# M3_Coral.net
KiCad netlist of a schematic drawn in Altium Designer
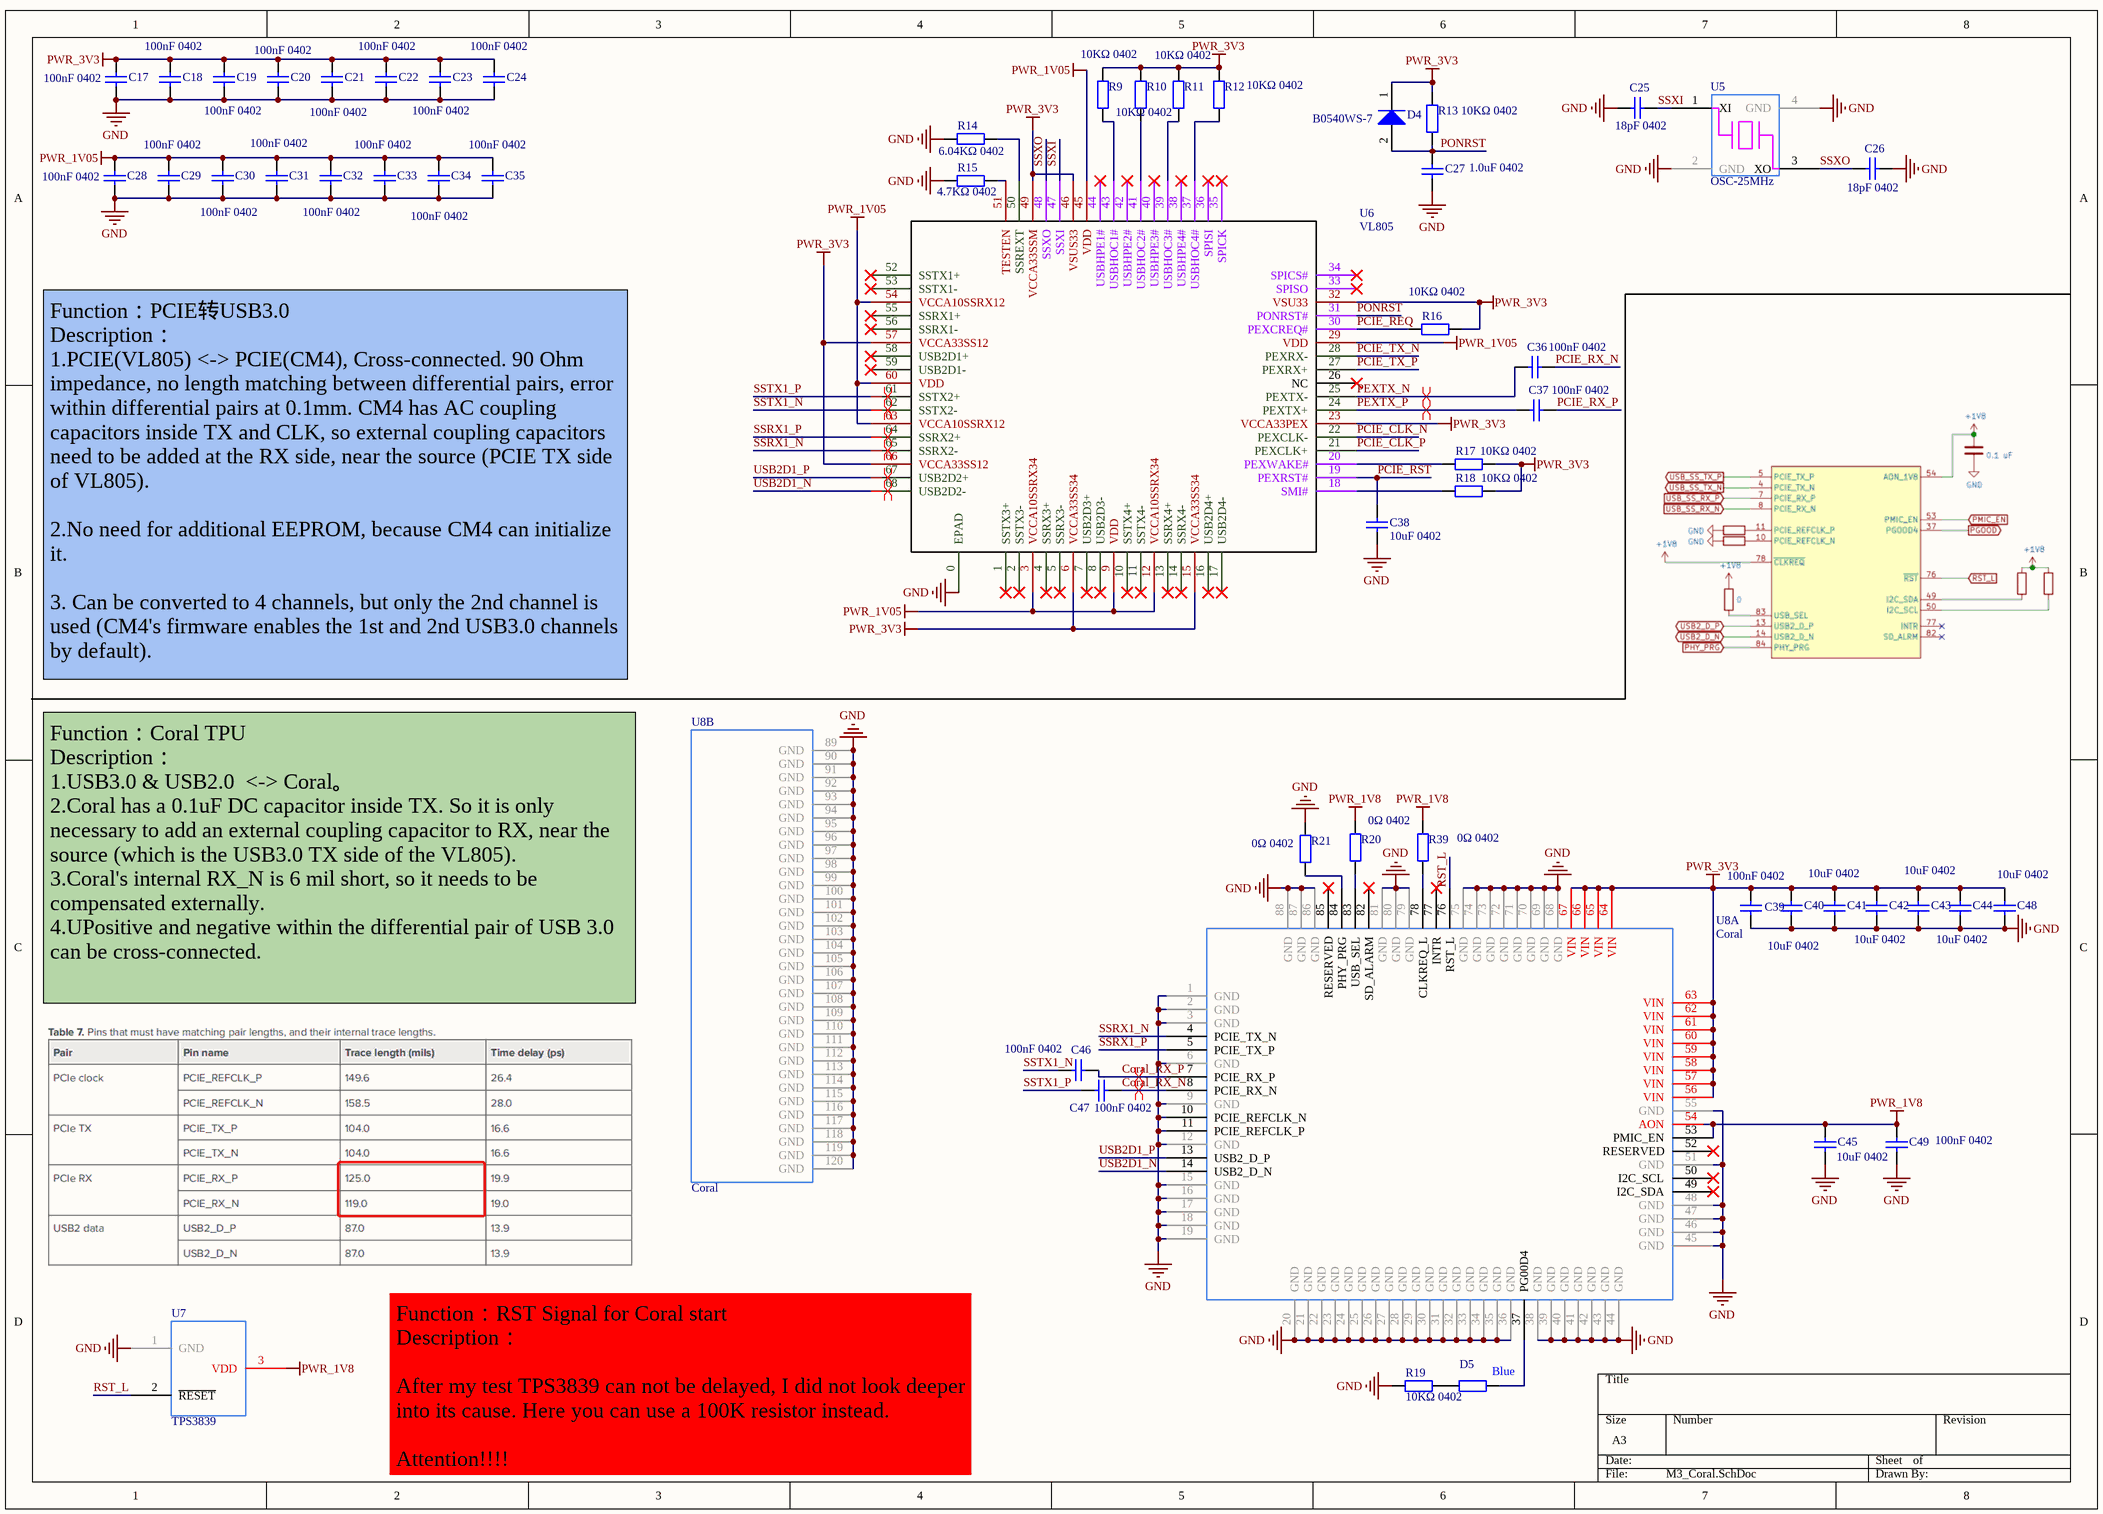
[diagram p0: M3_Coral.SchDoc]

(export (version "E")
  (design (tool "Eeschema 10.0.6"))
  (components
    (comp (ref "C17")
      (value "100nF 0402")
      (footprint "0402_C")
      (description "贴片电容")
      (libsource (lib "Miscellaneous Devices LC") (part "0402 100nF (104) 10% 16V"))
    )
    (comp (ref "C18")
      (value "100nF 0402")
      (footprint "0402_C")
      (description "贴片电容")
      (libsource (lib "Miscellaneous Devices LC") (part "0402 100nF (104) 10% 16V"))
    )
    (comp (ref "C19")
      (value "100nF 0402")
      (footprint "0402_C")
      (description "贴片电容")
      (libsource (lib "Miscellaneous Devices LC") (part "0402 100nF (104) 10% 16V"))
    )
    (comp (ref "C20")
      (value "100nF 0402")
      (footprint "0402_C")
      (description "贴片电容")
      (libsource (lib "Miscellaneous Devices LC") (part "0402 100nF (104) 10% 16V"))
    )
    (comp (ref "C21")
      (value "100nF 0402")
      (footprint "0402_C")
      (description "贴片电容")
      (libsource (lib "Miscellaneous Devices LC") (part "0402 100nF (104) 10% 16V"))
    )
    (comp (ref "C22")
      (value "100nF 0402")
      (footprint "0402_C")
      (description "贴片电容")
      (libsource (lib "Miscellaneous Devices LC") (part "0402 100nF (104) 10% 16V"))
    )
    (comp (ref "C23")
      (value "100nF 0402")
      (footprint "0402_C")
      (description "贴片电容")
      (libsource (lib "Miscellaneous Devices LC") (part "0402 100nF (104) 10% 16V"))
    )
    (comp (ref "C24")
      (value "100nF 0402")
      (footprint "0402_C")
      (description "贴片电容")
      (libsource (lib "Miscellaneous Devices LC") (part "0402 100nF (104) 10% 16V"))
    )
    (comp (ref "C25")
      (value "18pF 0402")
      (footprint "0402_C")
      (description "贴片电容")
      (libsource (lib "Miscellaneous Devices LC") (part "0402 18pF (180) 5% 50V"))
    )
    (comp (ref "C26")
      (value "18pF 0402")
      (footprint "0402_C")
      (description "贴片电容")
      (libsource (lib "Miscellaneous Devices LC") (part "0402 18pF (180) 5% 50V"))
    )
    (comp (ref "C27")
      (value "1.0uF 0402")
      (footprint "0402_C")
      (description "贴片电容")
      (libsource (lib "Miscellaneous Devices LC") (part "0402 1.0uF (105) 10% 25V"))
    )
    (comp (ref "C28")
      (value "100nF 0402")
      (footprint "0402_C")
      (description "贴片电容")
      (libsource (lib "Miscellaneous Devices LC") (part "0402 100nF (104) 10% 16V"))
    )
    (comp (ref "C29")
      (value "100nF 0402")
      (footprint "0402_C")
      (description "贴片电容")
      (libsource (lib "Miscellaneous Devices LC") (part "0402 100nF (104) 10% 16V"))
    )
    (comp (ref "C30")
      (value "100nF 0402")
      (footprint "0402_C")
      (description "贴片电容")
      (libsource (lib "Miscellaneous Devices LC") (part "0402 100nF (104) 10% 16V"))
    )
    (comp (ref "C31")
      (value "100nF 0402")
      (footprint "0402_C")
      (description "贴片电容")
      (libsource (lib "Miscellaneous Devices LC") (part "0402 100nF (104) 10% 16V"))
    )
    (comp (ref "C32")
      (value "100nF 0402")
      (footprint "0402_C")
      (description "贴片电容")
      (libsource (lib "Miscellaneous Devices LC") (part "0402 100nF (104) 10% 16V"))
    )
    (comp (ref "C33")
      (value "100nF 0402")
      (footprint "0402_C")
      (description "贴片电容")
      (libsource (lib "Miscellaneous Devices LC") (part "0402 100nF (104) 10% 16V"))
    )
    (comp (ref "C34")
      (value "100nF 0402")
      (footprint "0402_C")
      (description "贴片电容")
      (libsource (lib "Miscellaneous Devices LC") (part "0402 100nF (104) 10% 16V"))
    )
    (comp (ref "C35")
      (value "100nF 0402")
      (footprint "0402_C")
      (description "贴片电容")
      (libsource (lib "Miscellaneous Devices LC") (part "0402 100nF (104) 10% 16V"))
    )
    (comp (ref "C36")
      (value "100nF 0402")
      (footprint "0402_C")
      (description "贴片电容")
      (libsource (lib "Miscellaneous Devices LC") (part "0402 100nF (104) 10% 16V"))
    )
    (comp (ref "C37")
      (value "100nF 0402")
      (footprint "0402_C")
      (description "贴片电容")
      (libsource (lib "Miscellaneous Devices LC") (part "0402 100nF (104) 10% 16V"))
    )
    (comp (ref "C38")
      (value "10uF 0402")
      (footprint "0402_C")
      (description "贴片电容")
      (libsource (lib "Miscellaneous Devices LC") (part "0402 10uF (106) 20% 6.3V"))
    )
    (comp (ref "C39")
      (value "100nF 0402")
      (footprint "0402_C")
      (description "贴片电容")
      (libsource (lib "Miscellaneous Devices LC") (part "0402 100nF (104) 10% 16V"))
    )
    (comp (ref "C40")
      (value "10uF 0402")
      (footprint "0402_C")
      (description "贴片电容")
      (libsource (lib "Miscellaneous Devices LC") (part "0402 10uF (106) 20% 6.3V"))
    )
    (comp (ref "C41")
      (value "10uF 0402")
      (footprint "0402_C")
      (description "贴片电容")
      (libsource (lib "Miscellaneous Devices LC") (part "0402 10uF (106) 20% 6.3V"))
    )
    (comp (ref "C42")
      (value "10uF 0402")
      (footprint "0402_C")
      (description "贴片电容")
      (libsource (lib "Miscellaneous Devices LC") (part "0402 10uF (106) 20% 6.3V"))
    )
    (comp (ref "C43")
      (value "10uF 0402")
      (footprint "0402_C")
      (description "贴片电容")
      (libsource (lib "Miscellaneous Devices LC") (part "0402 10uF (106) 20% 6.3V"))
    )
    (comp (ref "C44")
      (value "10uF 0402")
      (footprint "0402_C")
      (description "贴片电容")
      (libsource (lib "Miscellaneous Devices LC") (part "0402 10uF (106) 20% 6.3V"))
    )
    (comp (ref "C45")
      (value "10uF 0402")
      (footprint "0402_C")
      (description "贴片电容")
      (libsource (lib "Miscellaneous Devices LC") (part "0402 10uF (106) 20% 6.3V"))
    )
    (comp (ref "C46")
      (value "100nF 0402")
      (footprint "0402_C")
      (description "贴片电容")
      (libsource (lib "Miscellaneous Devices LC") (part "0402 100nF (104) 10% 16V"))
    )
    (comp (ref "C47")
      (value "100nF 0402")
      (footprint "0402_C")
      (description "贴片电容")
      (libsource (lib "Miscellaneous Devices LC") (part "0402 100nF (104) 10% 16V"))
    )
    (comp (ref "C48")
      (value "10uF 0402")
      (footprint "0402_C")
      (description "贴片电容")
      (libsource (lib "Miscellaneous Devices LC") (part "0402 10uF (106) 20% 6.3V"))
    )
    (comp (ref "C49")
      (value "100nF 0402")
      (footprint "0402_C")
      (description "贴片电容")
      (libsource (lib "Miscellaneous Devices LC") (part "0402 100nF (104) 10% 16V"))
    )
    (comp (ref "D4") (value "B0540WS-7") (footprint "B0540WS-7") (libsource (lib "Mars") (part "B0540WS-7")))
    (comp (ref "D5")
      (value "Blue")
      (footprint "0402_R")
      (description "贴片电阻")
      (libsource (lib "") (part "0402 10KΩ (1002) 1%_1"))
    )
    (comp (ref "R9")
      (value "10KΩ 0402")
      (footprint "0402_R")
      (description "贴片电阻")
      (libsource (lib "Miscellaneous Devices LC") (part "0402 10KΩ (1002) 1%"))
    )
    (comp (ref "R10")
      (value "10KΩ 0402")
      (footprint "0402_R")
      (description "贴片电阻")
      (libsource (lib "Miscellaneous Devices LC") (part "0402 10KΩ (1002) 1%"))
    )
    (comp (ref "R11")
      (value "10KΩ 0402")
      (footprint "0402_R")
      (description "贴片电阻")
      (libsource (lib "Miscellaneous Devices LC") (part "0402 10KΩ (1002) 1%"))
    )
    (comp (ref "R12")
      (value "10KΩ 0402")
      (footprint "0402_R")
      (description "贴片电阻")
      (libsource (lib "Miscellaneous Devices LC") (part "0402 10KΩ (1002) 1%"))
    )
    (comp (ref "R13")
      (value "10KΩ 0402")
      (footprint "0402_R")
      (description "贴片电阻")
      (libsource (lib "Miscellaneous Devices LC") (part "0402 10KΩ (1002) 1%"))
    )
    (comp (ref "R14")
      (value "6.04KΩ 0402")
      (footprint "0402_R")
      (description "贴片电阻")
      (libsource (lib "Miscellaneous Devices LC") (part "0402 5.6KΩ (5601) 1%"))
    )
    (comp (ref "R15")
      (value "4.7KΩ 0402")
      (footprint "0402_R")
      (description "贴片电阻")
      (libsource (lib "Miscellaneous Devices LC") (part "0402 4.7KΩ (4701) 1%"))
    )
    (comp (ref "R16")
      (value "10KΩ 0402")
      (footprint "0402_R")
      (description "贴片电阻")
      (libsource (lib "") (part "0402 10KΩ (1002) 1%_1"))
    )
    (comp (ref "R17")
      (value "10KΩ 0402")
      (footprint "0402_R")
      (description "贴片电阻")
      (libsource (lib "") (part "0402 10KΩ (1002) 1%_1"))
    )
    (comp (ref "R18")
      (value "10KΩ 0402")
      (footprint "0402_R")
      (description "贴片电阻")
      (libsource (lib "") (part "0402 10KΩ (1002) 1%_1"))
    )
    (comp (ref "R19")
      (value "10KΩ 0402")
      (footprint "0402_R")
      (description "贴片电阻")
      (libsource (lib "") (part "0402 10KΩ (1002) 1%_1"))
    )
    (comp (ref "R20")
      (value "0Ω 0402")
      (footprint "0402_R")
      (description "贴片电阻")
      (libsource (lib "Miscellaneous Devices LC") (part "0402 0Ω (0R0) 1%"))
    )
    (comp (ref "R21")
      (value "0Ω 0402")
      (footprint "0402_R")
      (description "贴片电阻")
      (libsource (lib "Miscellaneous Devices LC") (part "0402 0Ω (0R0) 1%"))
    )
    (comp (ref "R39")
      (value "0Ω 0402")
      (footprint "0402_R")
      (description "贴片电阻")
      (libsource (lib "Miscellaneous Devices LC") (part "0402 0Ω (0R0) 1%"))
    )
    (comp (ref "U5")
      (value "OSC-25MHz")
      (footprint "OSC-25MHz")
      (description "Passive crystal oscillator")
      (libsource (lib "Mars") (part "OSC-25MHz"))
    )
    (comp (ref "U6")
      (value "VL805")
      (footprint "VL805")
      (description "PCIe to USB3.0")
      (libsource (lib "Mars") (part "VL805"))
    )
    (comp (ref "U7")
      (value "TPS3839")
      (footprint "TPS3839")
      (description "Delay 200 MS")
      (libsource (lib "Mars") (part "TPS3839"))
    )
    (comp (ref "U8")
      (value "Coral")
      (footprint "Coral")
      (description "G313-06329-00")
      (libsource (lib "Mars") (part "Coral"))
    )
  )
  (nets
    (net (code "1") (name "/Coral_RX_N") (class "Default")
      (node (ref "C47") (pin "2") (pinfunction "2_2") (pintype "passive"))
      (node (ref "U8") (pin "8") (pinfunction "PCIE_RX_N_8") (pintype "passive"))
    )
    (net (code "2") (name "/Coral_RX_P") (class "Default")
      (node (ref "C46") (pin "2") (pinfunction "2_2") (pintype "passive"))
      (node (ref "U8") (pin "7") (pinfunction "PCIE_RX_P_7") (pintype "passive"))
    )
    (net (code "3") (name "/PCIE_CLK_N") (class "Default")
      (node (ref "U6") (pin "22") (pinfunction "PEXCLK-_22") (pintype "passive"))
    )
    (net (code "4") (name "/PCIE_CLK_P") (class "Default")
      (node (ref "U6") (pin "21") (pinfunction "PEXCLK+_21") (pintype "passive"))
    )
    (net (code "5") (name "/PCIE_REQ") (class "Default")
      (node (ref "R16") (pin "1") (pinfunction "1_1") (pintype "passive"))
      (node (ref "U6") (pin "30") (pinfunction "PEXCREQ#_30") (pintype "passive"))
    )
    (net (code "6") (name "/PCIE_RST") (class "Default")
      (node (ref "C38") (pin "2") (pinfunction "2_2") (pintype "passive"))
      (node (ref "U6") (pin "19") (pinfunction "PEXRST#_19") (pintype "passive"))
    )
    (net (code "7") (name "/PCIE_RX_N") (class "Default")
      (node (ref "C36") (pin "2") (pinfunction "2_2") (pintype "passive"))
    )
    (net (code "8") (name "/PCIE_RX_P") (class "Default")
      (node (ref "C37") (pin "2") (pinfunction "2_2") (pintype "passive"))
    )
    (net (code "9") (name "/PCIE_TX_N") (class "Default")
      (node (ref "U6") (pin "28") (pinfunction "PEXRX-_28") (pintype "passive"))
    )
    (net (code "10") (name "/PCIE_TX_P") (class "Default")
      (node (ref "U6") (pin "27") (pinfunction "PEXRX+_27") (pintype "passive"))
    )
    (net (code "11") (name "/PEXTX_N") (class "Default")
      (node (ref "C36") (pin "1") (pinfunction "1_1") (pintype "passive"))
      (node (ref "U6") (pin "25") (pinfunction "PEXTX-_25") (pintype "passive"))
    )
    (net (code "12") (name "/PEXTX_P") (class "Default")
      (node (ref "C37") (pin "1") (pinfunction "1_1") (pintype "passive"))
      (node (ref "U6") (pin "24") (pinfunction "PEXTX+_24") (pintype "passive"))
    )
    (net (code "13") (name "/PONRST") (class "Default")
      (node (ref "C27") (pin "1") (pinfunction "1_1") (pintype "passive"))
      (node (ref "D4") (pin "2") (pinfunction "A_2") (pintype "passive"))
      (node (ref "R13") (pin "1") (pinfunction "1_1") (pintype "passive"))
      (node (ref "U6") (pin "31") (pinfunction "PONRST#_31") (pintype "passive"))
    )
    (net (code "14") (name "/RST_L") (class "Default")
      (node (ref "U7") (pin "2") (pinfunction "~{RESET}_2") (pintype "passive"))
      (node (ref "U8") (pin "76") (pinfunction "RST_L_76") (pintype "power_in"))
    )
    (net (code "15") (name "/SSRX1_N") (class "Default")
      (node (ref "U6") (pin "65") (pinfunction "SSRX2-_65") (pintype "passive"))
      (node (ref "U8") (pin "4") (pinfunction "PCIE_TX_N_4") (pintype "passive"))
    )
    (net (code "16") (name "/SSRX1_P") (class "Default")
      (node (ref "U6") (pin "64") (pinfunction "SSRX2+_64") (pintype "passive"))
      (node (ref "U8") (pin "5") (pinfunction "PCIE_TX_P_5") (pintype "passive"))
    )
    (net (code "17") (name "/SSTX1_N") (class "Default")
      (node (ref "C46") (pin "1") (pinfunction "1_1") (pintype "passive"))
      (node (ref "U6") (pin "62") (pinfunction "SSTX2-_62") (pintype "passive"))
    )
    (net (code "18") (name "/SSTX1_P") (class "Default")
      (node (ref "C47") (pin "1") (pinfunction "1_1") (pintype "passive"))
      (node (ref "U6") (pin "61") (pinfunction "SSTX2+_61") (pintype "passive"))
    )
    (net (code "19") (name "/SSXI") (class "Default")
      (node (ref "C25") (pin "2") (pinfunction "2_2") (pintype "passive"))
      (node (ref "U5") (pin "1") (pinfunction "XI_1") (pintype "passive"))
      (node (ref "U6") (pin "47") (pinfunction "SSXI_47") (pintype "passive"))
    )
    (net (code "20") (name "/SSXO") (class "Default")
      (node (ref "C26") (pin "1") (pinfunction "1_1") (pintype "passive"))
      (node (ref "U5") (pin "3") (pinfunction "XO_3") (pintype "passive"))
      (node (ref "U6") (pin "48") (pinfunction "SSXO_48") (pintype "passive"))
    )
    (net (code "21") (name "/USB2D1_N") (class "Default")
      (node (ref "U6") (pin "68") (pinfunction "USB2D2-_68") (pintype "passive"))
      (node (ref "U8") (pin "14") (pinfunction "USB2_D_N_14") (pintype "passive"))
    )
    (net (code "22") (name "/USB2D1_P") (class "Default")
      (node (ref "U6") (pin "67") (pinfunction "USB2D2+_67") (pintype "passive"))
      (node (ref "U8") (pin "13") (pinfunction "USB2_D_P_13") (pintype "passive"))
    )
    (net (code "23") (name "GND") (class "Default")
      (node (ref "C17") (pin "1") (pinfunction "1_1") (pintype "passive"))
      (node (ref "C18") (pin "1") (pinfunction "1_1") (pintype "passive"))
      (node (ref "C19") (pin "1") (pinfunction "1_1") (pintype "passive"))
      (node (ref "C20") (pin "1") (pinfunction "1_1") (pintype "passive"))
      (node (ref "C21") (pin "1") (pinfunction "1_1") (pintype "passive"))
      (node (ref "C22") (pin "1") (pinfunction "1_1") (pintype "passive"))
      (node (ref "C23") (pin "1") (pinfunction "1_1") (pintype "passive"))
      (node (ref "C24") (pin "1") (pinfunction "1_1") (pintype "passive"))
      (node (ref "C25") (pin "1") (pinfunction "1_1") (pintype "passive"))
      (node (ref "C26") (pin "2") (pinfunction "2_2") (pintype "passive"))
      (node (ref "C27") (pin "2") (pinfunction "2_2") (pintype "passive"))
      (node (ref "C28") (pin "1") (pinfunction "1_1") (pintype "passive"))
      (node (ref "C29") (pin "1") (pinfunction "1_1") (pintype "passive"))
      (node (ref "C30") (pin "1") (pinfunction "1_1") (pintype "passive"))
      (node (ref "C31") (pin "1") (pinfunction "1_1") (pintype "passive"))
      (node (ref "C32") (pin "1") (pinfunction "1_1") (pintype "passive"))
      (node (ref "C33") (pin "1") (pinfunction "1_1") (pintype "passive"))
      (node (ref "C34") (pin "1") (pinfunction "1_1") (pintype "passive"))
      (node (ref "C35") (pin "1") (pinfunction "1_1") (pintype "passive"))
      (node (ref "C38") (pin "1") (pinfunction "1_1") (pintype "passive"))
      (node (ref "C39") (pin "1") (pinfunction "1_1") (pintype "passive"))
      (node (ref "C40") (pin "1") (pinfunction "1_1") (pintype "passive"))
      (node (ref "C41") (pin "1") (pinfunction "1_1") (pintype "passive"))
      (node (ref "C42") (pin "1") (pinfunction "1_1") (pintype "passive"))
      (node (ref "C43") (pin "1") (pinfunction "1_1") (pintype "passive"))
      (node (ref "C44") (pin "1") (pinfunction "1_1") (pintype "passive"))
      (node (ref "C45") (pin "1") (pinfunction "1_1") (pintype "passive"))
      (node (ref "C48") (pin "1") (pinfunction "1_1") (pintype "passive"))
      (node (ref "C49") (pin "1") (pinfunction "1_1") (pintype "passive"))
      (node (ref "R14") (pin "2") (pinfunction "2_2") (pintype "passive"))
      (node (ref "R15") (pin "2") (pinfunction "2_2") (pintype "passive"))
      (node (ref "R19") (pin "1") (pinfunction "1_1") (pintype "passive"))
      (node (ref "R21") (pin "2") (pinfunction "2_2") (pintype "passive"))
      (node (ref "U5") (pin "2") (pinfunction "GND_2") (pintype "passive"))
      (node (ref "U5") (pin "4") (pinfunction "GND_4") (pintype "passive"))
      (node (ref "U6") (pin "0") (pinfunction "EPAD_0") (pintype "passive"))
      (node (ref "U7") (pin "1") (pinfunction "GND_1") (pintype "passive"))
      (node (ref "U8") (pin "1") (pinfunction "GND_1") (pintype "power_in"))
      (node (ref "U8") (pin "10") (pinfunction "PCIE_REFCLK_N_10") (pintype "passive"))
      (node (ref "U8") (pin "100") (pinfunction "GND_100") (pintype "power_in"))
      (node (ref "U8") (pin "101") (pinfunction "GND_101") (pintype "power_in"))
      (node (ref "U8") (pin "102") (pinfunction "GND_102") (pintype "power_in"))
      (node (ref "U8") (pin "103") (pinfunction "GND_103") (pintype "power_in"))
      (node (ref "U8") (pin "104") (pinfunction "GND_104") (pintype "power_in"))
      (node (ref "U8") (pin "105") (pinfunction "GND_105") (pintype "power_in"))
      (node (ref "U8") (pin "106") (pinfunction "GND_106") (pintype "power_in"))
      (node (ref "U8") (pin "107") (pinfunction "GND_107") (pintype "power_in"))
      (node (ref "U8") (pin "108") (pinfunction "GND_108") (pintype "power_in"))
      (node (ref "U8") (pin "109") (pinfunction "GND_109") (pintype "power_in"))
      (node (ref "U8") (pin "11") (pinfunction "PCIE_REFCLK_P_11") (pintype "passive"))
      (node (ref "U8") (pin "110") (pinfunction "GND_110") (pintype "power_in"))
      (node (ref "U8") (pin "111") (pinfunction "GND_111") (pintype "power_in"))
      (node (ref "U8") (pin "112") (pinfunction "GND_112") (pintype "power_in"))
      (node (ref "U8") (pin "113") (pinfunction "GND_113") (pintype "power_in"))
      (node (ref "U8") (pin "114") (pinfunction "GND_114") (pintype "power_in"))
      (node (ref "U8") (pin "115") (pinfunction "GND_115") (pintype "power_in"))
      (node (ref "U8") (pin "116") (pinfunction "GND_116") (pintype "power_in"))
      (node (ref "U8") (pin "117") (pinfunction "GND_117") (pintype "power_in"))
      (node (ref "U8") (pin "118") (pinfunction "GND_118") (pintype "power_in"))
      (node (ref "U8") (pin "119") (pinfunction "GND_119") (pintype "power_in"))
      (node (ref "U8") (pin "12") (pinfunction "GND_12") (pintype "passive"))
      (node (ref "U8") (pin "120") (pinfunction "GND_120") (pintype "power_in"))
      (node (ref "U8") (pin "15") (pinfunction "GND_15") (pintype "passive"))
      (node (ref "U8") (pin "16") (pinfunction "GND_16") (pintype "passive"))
      (node (ref "U8") (pin "17") (pinfunction "GND_17") (pintype "passive"))
      (node (ref "U8") (pin "18") (pinfunction "GND_18") (pintype "passive"))
      (node (ref "U8") (pin "19") (pinfunction "GND_19") (pintype "passive"))
      (node (ref "U8") (pin "2") (pinfunction "GND_2") (pintype "passive"))
      (node (ref "U8") (pin "20") (pinfunction "GND_20") (pintype "power_in"))
      (node (ref "U8") (pin "21") (pinfunction "GND_21") (pintype "power_in"))
      (node (ref "U8") (pin "22") (pinfunction "GND_22") (pintype "power_in"))
      (node (ref "U8") (pin "23") (pinfunction "GND_23") (pintype "power_in"))
      (node (ref "U8") (pin "24") (pinfunction "GND_24") (pintype "power_in"))
      (node (ref "U8") (pin "25") (pinfunction "GND_25") (pintype "power_in"))
      (node (ref "U8") (pin "26") (pinfunction "GND_26") (pintype "power_in"))
      (node (ref "U8") (pin "27") (pinfunction "GND_27") (pintype "power_in"))
      (node (ref "U8") (pin "28") (pinfunction "GND_28") (pintype "power_in"))
      (node (ref "U8") (pin "29") (pinfunction "GND_29") (pintype "power_in"))
      (node (ref "U8") (pin "3") (pinfunction "GND_3") (pintype "passive"))
      (node (ref "U8") (pin "30") (pinfunction "GND_30") (pintype "power_in"))
      (node (ref "U8") (pin "31") (pinfunction "GND_31") (pintype "power_in"))
      (node (ref "U8") (pin "32") (pinfunction "GND_32") (pintype "power_in"))
      (node (ref "U8") (pin "33") (pinfunction "GND_33") (pintype "power_in"))
      (node (ref "U8") (pin "34") (pinfunction "GND_34") (pintype "power_in"))
      (node (ref "U8") (pin "35") (pinfunction "GND_35") (pintype "power_in"))
      (node (ref "U8") (pin "36") (pinfunction "GND_36") (pintype "power_in"))
      (node (ref "U8") (pin "38") (pinfunction "GND_38") (pintype "power_in"))
      (node (ref "U8") (pin "39") (pinfunction "GND_39") (pintype "power_in"))
      (node (ref "U8") (pin "40") (pinfunction "GND_40") (pintype "power_in"))
      (node (ref "U8") (pin "41") (pinfunction "GND_41") (pintype "power_in"))
      (node (ref "U8") (pin "42") (pinfunction "GND_42") (pintype "power_in"))
      (node (ref "U8") (pin "43") (pinfunction "GND_43") (pintype "power_in"))
      (node (ref "U8") (pin "44") (pinfunction "GND_44") (pintype "power_in"))
      (node (ref "U8") (pin "45") (pinfunction "GND_45") (pintype "power_in"))
      (node (ref "U8") (pin "46") (pinfunction "GND_46") (pintype "passive"))
      (node (ref "U8") (pin "47") (pinfunction "GND_47") (pintype "passive"))
      (node (ref "U8") (pin "48") (pinfunction "GND_48") (pintype "passive"))
      (node (ref "U8") (pin "51") (pinfunction "GND_51") (pintype "passive"))
      (node (ref "U8") (pin "55") (pinfunction "GND_55") (pintype "passive"))
      (node (ref "U8") (pin "6") (pinfunction "GND_6") (pintype "passive"))
      (node (ref "U8") (pin "68") (pinfunction "GND_68") (pintype "power_in"))
      (node (ref "U8") (pin "69") (pinfunction "GND_69") (pintype "power_in"))
      (node (ref "U8") (pin "70") (pinfunction "GND_70") (pintype "power_in"))
      (node (ref "U8") (pin "71") (pinfunction "GND_71") (pintype "power_in"))
      (node (ref "U8") (pin "72") (pinfunction "GND_72") (pintype "power_in"))
      (node (ref "U8") (pin "73") (pinfunction "GND_73") (pintype "power_in"))
      (node (ref "U8") (pin "74") (pinfunction "GND_74") (pintype "power_in"))
      (node (ref "U8") (pin "75") (pinfunction "GND_75") (pintype "power_in"))
      (node (ref "U8") (pin "79") (pinfunction "GND_79") (pintype "power_in"))
      (node (ref "U8") (pin "80") (pinfunction "GND_80") (pintype "power_in"))
      (node (ref "U8") (pin "81") (pinfunction "GND_81") (pintype "power_in"))
      (node (ref "U8") (pin "86") (pinfunction "GND_86") (pintype "power_in"))
      (node (ref "U8") (pin "87") (pinfunction "GND_87") (pintype "power_in"))
      (node (ref "U8") (pin "88") (pinfunction "GND_88") (pintype "power_in"))
      (node (ref "U8") (pin "89") (pinfunction "GND_89") (pintype "power_in"))
      (node (ref "U8") (pin "9") (pinfunction "GND_9") (pintype "passive"))
      (node (ref "U8") (pin "90") (pinfunction "GND_90") (pintype "power_in"))
      (node (ref "U8") (pin "91") (pinfunction "GND_91") (pintype "power_in"))
      (node (ref "U8") (pin "92") (pinfunction "GND_92") (pintype "power_in"))
      (node (ref "U8") (pin "93") (pinfunction "GND_93") (pintype "power_in"))
      (node (ref "U8") (pin "94") (pinfunction "GND_94") (pintype "power_in"))
      (node (ref "U8") (pin "95") (pinfunction "GND_95") (pintype "power_in"))
      (node (ref "U8") (pin "96") (pinfunction "GND_96") (pintype "power_in"))
      (node (ref "U8") (pin "97") (pinfunction "GND_97") (pintype "power_in"))
      (node (ref "U8") (pin "98") (pinfunction "GND_98") (pintype "power_in"))
      (node (ref "U8") (pin "99") (pinfunction "GND_99") (pintype "power_in"))
    )
    (net (code "24") (name "Net-(D5-Pad1)") (class "Default")
      (node (ref "D5") (pin "1") (pinfunction "1_1") (pintype "passive"))
      (node (ref "R19") (pin "2") (pinfunction "2_2") (pintype "passive"))
    )
    (net (code "25") (name "Net-(U6-PEXWAKE#)") (class "Default")
      (node (ref "R17") (pin "1") (pinfunction "1_1") (pintype "passive"))
      (node (ref "U6") (pin "20") (pinfunction "PEXWAKE#_20") (pintype "passive"))
    )
    (net (code "26") (name "Net-(U6-SMI#)") (class "Default")
      (node (ref "R18") (pin "1") (pinfunction "1_1") (pintype "passive"))
      (node (ref "U6") (pin "18") (pinfunction "SMI#_18") (pintype "passive"))
    )
    (net (code "27") (name "Net-(U6-SSREXT)") (class "Default")
      (node (ref "R14") (pin "1") (pinfunction "1_1") (pintype "passive"))
      (node (ref "U6") (pin "50") (pinfunction "SSREXT_50") (pintype "passive"))
    )
    (net (code "28") (name "Net-(U6-TESTEN)") (class "Default")
      (node (ref "R15") (pin "1") (pinfunction "1_1") (pintype "passive"))
      (node (ref "U6") (pin "51") (pinfunction "TESTEN_51") (pintype "passive"))
    )
    (net (code "29") (name "Net-(U6-USBHOC1#)") (class "Default")
      (node (ref "R9") (pin "1") (pinfunction "1_1") (pintype "passive"))
      (node (ref "U6") (pin "43") (pinfunction "USBHOC1#_43") (pintype "passive"))
    )
    (net (code "30") (name "Net-(U6-USBHOC2#)") (class "Default")
      (node (ref "R10") (pin "1") (pinfunction "1_1") (pintype "passive"))
      (node (ref "U6") (pin "41") (pinfunction "USBHOC2#_41") (pintype "passive"))
    )
    (net (code "31") (name "Net-(U6-USBHOC3#)") (class "Default")
      (node (ref "R11") (pin "1") (pinfunction "1_1") (pintype "passive"))
      (node (ref "U6") (pin "39") (pinfunction "USBHOC3#_39") (pintype "passive"))
    )
    (net (code "32") (name "Net-(U6-USBHOC4#)") (class "Default")
      (node (ref "R12") (pin "1") (pinfunction "1_1") (pintype "passive"))
      (node (ref "U6") (pin "37") (pinfunction "USBHOC4#_37") (pintype "passive"))
    )
    (net (code "33") (name "Net-(U8A-CLKREQ_L)") (class "Default")
      (node (ref "R39") (pin "1") (pinfunction "1_1") (pintype "passive"))
      (node (ref "U8") (pin "78") (pinfunction "CLKREQ_L_78") (pintype "power_in"))
    )
    (net (code "34") (name "Net-(U8A-PG00D4)") (class "Default")
      (node (ref "D5") (pin "2") (pinfunction "2_2") (pintype "passive"))
      (node (ref "U8") (pin "37") (pinfunction "PG00D4_37") (pintype "power_in"))
    )
    (net (code "35") (name "Net-(U8A-PHY_PRG)") (class "Default")
      (node (ref "R21") (pin "1") (pinfunction "1_1") (pintype "passive"))
      (node (ref "U8") (pin "84") (pinfunction "PHY_PRG_84") (pintype "power_in"))
    )
    (net (code "36") (name "Net-(U8A-USB_SEL)") (class "Default")
      (node (ref "R20") (pin "1") (pinfunction "1_1") (pintype "passive"))
      (node (ref "U8") (pin "83") (pinfunction "USB_SEL_83") (pintype "power_in"))
    )
    (net (code "37") (name "PWR_1V05") (class "Default")
      (node (ref "C28") (pin "2") (pinfunction "2_2") (pintype "passive"))
      (node (ref "C29") (pin "2") (pinfunction "2_2") (pintype "passive"))
      (node (ref "C30") (pin "2") (pinfunction "2_2") (pintype "passive"))
      (node (ref "C31") (pin "2") (pinfunction "2_2") (pintype "passive"))
      (node (ref "C32") (pin "2") (pinfunction "2_2") (pintype "passive"))
      (node (ref "C33") (pin "2") (pinfunction "2_2") (pintype "passive"))
      (node (ref "C34") (pin "2") (pinfunction "2_2") (pintype "passive"))
      (node (ref "C35") (pin "2") (pinfunction "2_2") (pintype "passive"))
      (node (ref "U6") (pin "12") (pinfunction "VCCA10SSRX34_12") (pintype "passive"))
      (node (ref "U6") (pin "29") (pinfunction "VDD_29") (pintype "passive"))
      (node (ref "U6") (pin "3") (pinfunction "VCCA10SSRX34_3") (pintype "passive"))
      (node (ref "U6") (pin "45") (pinfunction "VDD_45") (pintype "passive"))
      (node (ref "U6") (pin "54") (pinfunction "VCCA10SSRX12_54") (pintype "passive"))
      (node (ref "U6") (pin "60") (pinfunction "VDD_60") (pintype "passive"))
      (node (ref "U6") (pin "63") (pinfunction "VCCA10SSRX12_63") (pintype "passive"))
      (node (ref "U6") (pin "9") (pinfunction "VDD_9") (pintype "passive"))
    )
    (net (code "38") (name "PWR_1V8") (class "Default")
      (node (ref "C45") (pin "2") (pinfunction "2_2") (pintype "passive"))
      (node (ref "C49") (pin "2") (pinfunction "2_2") (pintype "passive"))
      (node (ref "R20") (pin "2") (pinfunction "2_2") (pintype "passive"))
      (node (ref "R39") (pin "2") (pinfunction "2_2") (pintype "passive"))
      (node (ref "U7") (pin "3") (pinfunction "VDD_3") (pintype "passive"))
      (node (ref "U8") (pin "53") (pinfunction "PMIC_EN_53") (pintype "passive"))
      (node (ref "U8") (pin "54") (pinfunction "AON_54") (pintype "passive"))
    )
    (net (code "39") (name "PWR_3V3") (class "Default")
      (node (ref "C17") (pin "2") (pinfunction "2_2") (pintype "passive"))
      (node (ref "C18") (pin "2") (pinfunction "2_2") (pintype "passive"))
      (node (ref "C19") (pin "2") (pinfunction "2_2") (pintype "passive"))
      (node (ref "C20") (pin "2") (pinfunction "2_2") (pintype "passive"))
      (node (ref "C21") (pin "2") (pinfunction "2_2") (pintype "passive"))
      (node (ref "C22") (pin "2") (pinfunction "2_2") (pintype "passive"))
      (node (ref "C23") (pin "2") (pinfunction "2_2") (pintype "passive"))
      (node (ref "C24") (pin "2") (pinfunction "2_2") (pintype "passive"))
      (node (ref "C39") (pin "2") (pinfunction "2_2") (pintype "passive"))
      (node (ref "C40") (pin "2") (pinfunction "2_2") (pintype "passive"))
      (node (ref "C41") (pin "2") (pinfunction "2_2") (pintype "passive"))
      (node (ref "C42") (pin "2") (pinfunction "2_2") (pintype "passive"))
      (node (ref "C43") (pin "2") (pinfunction "2_2") (pintype "passive"))
      (node (ref "C44") (pin "2") (pinfunction "2_2") (pintype "passive"))
      (node (ref "C48") (pin "2") (pinfunction "2_2") (pintype "passive"))
      (node (ref "D4") (pin "1") (pinfunction "K_1") (pintype "passive"))
      (node (ref "R10") (pin "2") (pinfunction "2_2") (pintype "passive"))
      (node (ref "R11") (pin "2") (pinfunction "2_2") (pintype "passive"))
      (node (ref "R12") (pin "2") (pinfunction "2_2") (pintype "passive"))
      (node (ref "R13") (pin "2") (pinfunction "2_2") (pintype "passive"))
      (node (ref "R16") (pin "2") (pinfunction "2_2") (pintype "passive"))
      (node (ref "R17") (pin "2") (pinfunction "2_2") (pintype "passive"))
      (node (ref "R18") (pin "2") (pinfunction "2_2") (pintype "passive"))
      (node (ref "R9") (pin "2") (pinfunction "2_2") (pintype "passive"))
      (node (ref "U6") (pin "15") (pinfunction "VCCA33SS34_15") (pintype "passive"))
      (node (ref "U6") (pin "23") (pinfunction "VCCA33PEX_23") (pintype "passive"))
      (node (ref "U6") (pin "32") (pinfunction "VSU33_32") (pintype "passive"))
      (node (ref "U6") (pin "46") (pinfunction "VSUS33_46") (pintype "passive"))
      (node (ref "U6") (pin "49") (pinfunction "VCCA33SSM_49") (pintype "passive"))
      (node (ref "U6") (pin "57") (pinfunction "VCCA33SS12_57") (pintype "passive"))
      (node (ref "U6") (pin "6") (pinfunction "VCCA33SS34_6") (pintype "passive"))
      (node (ref "U6") (pin "66") (pinfunction "VCCA33SS12_66") (pintype "passive"))
      (node (ref "U8") (pin "56") (pinfunction "VIN_56") (pintype "passive"))
      (node (ref "U8") (pin "57") (pinfunction "VIN_57") (pintype "passive"))
      (node (ref "U8") (pin "58") (pinfunction "VIN_58") (pintype "passive"))
      (node (ref "U8") (pin "59") (pinfunction "VIN_59") (pintype "passive"))
      (node (ref "U8") (pin "60") (pinfunction "VIN_60") (pintype "passive"))
      (node (ref "U8") (pin "61") (pinfunction "VIN_61") (pintype "passive"))
      (node (ref "U8") (pin "62") (pinfunction "VIN_62") (pintype "passive"))
      (node (ref "U8") (pin "63") (pinfunction "VIN_63") (pintype "passive"))
      (node (ref "U8") (pin "64") (pinfunction "VIN_64") (pintype "power_in"))
      (node (ref "U8") (pin "65") (pinfunction "VIN_65") (pintype "power_in"))
      (node (ref "U8") (pin "66") (pinfunction "VIN_66") (pintype "power_in"))
      (node (ref "U8") (pin "67") (pinfunction "VIN_67") (pintype "power_in"))
    )
    (net (code "40") (name "unconnected-(U6-NC-Pad26)") (class "Default")
      (node (ref "U6") (pin "26") (pinfunction "NC_26") (pintype "passive+no_connect"))
    )
    (net (code "41") (name "unconnected-(U6-SPICK-Pad35)") (class "Default")
      (node (ref "U6") (pin "35") (pinfunction "SPICK_35") (pintype "passive+no_connect"))
    )
    (net (code "42") (name "unconnected-(U6-SPICS#-Pad34)") (class "Default")
      (node (ref "U6") (pin "34") (pinfunction "SPICS#_34") (pintype "passive+no_connect"))
    )
    (net (code "43") (name "unconnected-(U6-SPISI-Pad36)") (class "Default")
      (node (ref "U6") (pin "36") (pinfunction "SPISI_36") (pintype "passive+no_connect"))
    )
    (net (code "44") (name "unconnected-(U6-SPISO-Pad33)") (class "Default")
      (node (ref "U6") (pin "33") (pinfunction "SPISO_33") (pintype "passive+no_connect"))
    )
    (net (code "45") (name "unconnected-(U6-SSRX1+-Pad55)") (class "Default")
      (node (ref "U6") (pin "55") (pinfunction "SSRX1+_55") (pintype "passive+no_connect"))
    )
    (net (code "46") (name "unconnected-(U6-SSRX1--Pad56)") (class "Default")
      (node (ref "U6") (pin "56") (pinfunction "SSRX1-_56") (pintype "passive+no_connect"))
    )
    (net (code "47") (name "unconnected-(U6-SSRX3+-Pad4)") (class "Default")
      (node (ref "U6") (pin "4") (pinfunction "SSRX3+_4") (pintype "passive+no_connect"))
    )
    (net (code "48") (name "unconnected-(U6-SSRX3--Pad5)") (class "Default")
      (node (ref "U6") (pin "5") (pinfunction "SSRX3-_5") (pintype "passive+no_connect"))
    )
    (net (code "49") (name "unconnected-(U6-SSRX4+-Pad13)") (class "Default")
      (node (ref "U6") (pin "13") (pinfunction "SSRX4+_13") (pintype "passive+no_connect"))
    )
    (net (code "50") (name "unconnected-(U6-SSRX4--Pad14)") (class "Default")
      (node (ref "U6") (pin "14") (pinfunction "SSRX4-_14") (pintype "passive+no_connect"))
    )
    (net (code "51") (name "unconnected-(U6-SSTX1+-Pad52)") (class "Default")
      (node (ref "U6") (pin "52") (pinfunction "SSTX1+_52") (pintype "passive+no_connect"))
    )
    (net (code "52") (name "unconnected-(U6-SSTX1--Pad53)") (class "Default")
      (node (ref "U6") (pin "53") (pinfunction "SSTX1-_53") (pintype "passive+no_connect"))
    )
    (net (code "53") (name "unconnected-(U6-SSTX3+-Pad1)") (class "Default")
      (node (ref "U6") (pin "1") (pinfunction "SSTX3+_1") (pintype "passive+no_connect"))
    )
    (net (code "54") (name "unconnected-(U6-SSTX3--Pad2)") (class "Default")
      (node (ref "U6") (pin "2") (pinfunction "SSTX3-_2") (pintype "passive+no_connect"))
    )
    (net (code "55") (name "unconnected-(U6-SSTX4+-Pad10)") (class "Default")
      (node (ref "U6") (pin "10") (pinfunction "SSTX4+_10") (pintype "passive+no_connect"))
    )
    (net (code "56") (name "unconnected-(U6-SSTX4--Pad11)") (class "Default")
      (node (ref "U6") (pin "11") (pinfunction "SSTX4-_11") (pintype "passive+no_connect"))
    )
    (net (code "57") (name "unconnected-(U6-USB2D1+-Pad58)") (class "Default")
      (node (ref "U6") (pin "58") (pinfunction "USB2D1+_58") (pintype "passive+no_connect"))
    )
    (net (code "58") (name "unconnected-(U6-USB2D1--Pad59)") (class "Default")
      (node (ref "U6") (pin "59") (pinfunction "USB2D1-_59") (pintype "passive+no_connect"))
    )
    (net (code "59") (name "unconnected-(U6-USB2D3+-Pad7)") (class "Default")
      (node (ref "U6") (pin "7") (pinfunction "USB2D3+_7") (pintype "passive+no_connect"))
    )
    (net (code "60") (name "unconnected-(U6-USB2D3--Pad8)") (class "Default")
      (node (ref "U6") (pin "8") (pinfunction "USB2D3-_8") (pintype "passive+no_connect"))
    )
    (net (code "61") (name "unconnected-(U6-USB2D4+-Pad16)") (class "Default")
      (node (ref "U6") (pin "16") (pinfunction "USB2D4+_16") (pintype "passive+no_connect"))
    )
    (net (code "62") (name "unconnected-(U6-USB2D4--Pad17)") (class "Default")
      (node (ref "U6") (pin "17") (pinfunction "USB2D4-_17") (pintype "passive+no_connect"))
    )
    (net (code "63") (name "unconnected-(U6-USBHPE1#-Pad44)") (class "Default")
      (node (ref "U6") (pin "44") (pinfunction "USBHPE1#_44") (pintype "passive+no_connect"))
    )
    (net (code "64") (name "unconnected-(U6-USBHPE2#-Pad42)") (class "Default")
      (node (ref "U6") (pin "42") (pinfunction "USBHPE2#_42") (pintype "passive+no_connect"))
    )
    (net (code "65") (name "unconnected-(U6-USBHPE3#-Pad40)") (class "Default")
      (node (ref "U6") (pin "40") (pinfunction "USBHPE3#_40") (pintype "passive+no_connect"))
    )
    (net (code "66") (name "unconnected-(U6-USBHPE4#-Pad38)") (class "Default")
      (node (ref "U6") (pin "38") (pinfunction "USBHPE4#_38") (pintype "passive+no_connect"))
    )
    (net (code "67") (name "unconnected-(U8A-I2C_SCL-Pad50)") (class "Default")
      (node (ref "U8") (pin "50") (pinfunction "I2C_SCL_50") (pintype "passive+no_connect"))
    )
    (net (code "68") (name "unconnected-(U8A-I2C_SDA-Pad49)") (class "Default")
      (node (ref "U8") (pin "49") (pinfunction "I2C_SDA_49") (pintype "passive+no_connect"))
    )
    (net (code "69") (name "unconnected-(U8A-INTR-Pad77)") (class "Default")
      (node (ref "U8") (pin "77") (pinfunction "INTR_77") (pintype "power_in+no_connect"))
    )
    (net (code "70") (name "unconnected-(U8A-RESERVED-Pad52)") (class "Default")
      (node (ref "U8") (pin "52") (pinfunction "RESERVED_52") (pintype "passive+no_connect"))
    )
    (net (code "71") (name "unconnected-(U8A-RESERVED-Pad85)") (class "Default")
      (node (ref "U8") (pin "85") (pinfunction "RESERVED_85") (pintype "power_in+no_connect"))
    )
    (net (code "72") (name "unconnected-(U8A-SD_ALARM-Pad82)") (class "Default")
      (node (ref "U8") (pin "82") (pinfunction "SD_ALARM_82") (pintype "power_in+no_connect"))
    )
  )
)
